# evpr_mini_chopped.net
KiCad netlist of a schematic drawn in EAGLE
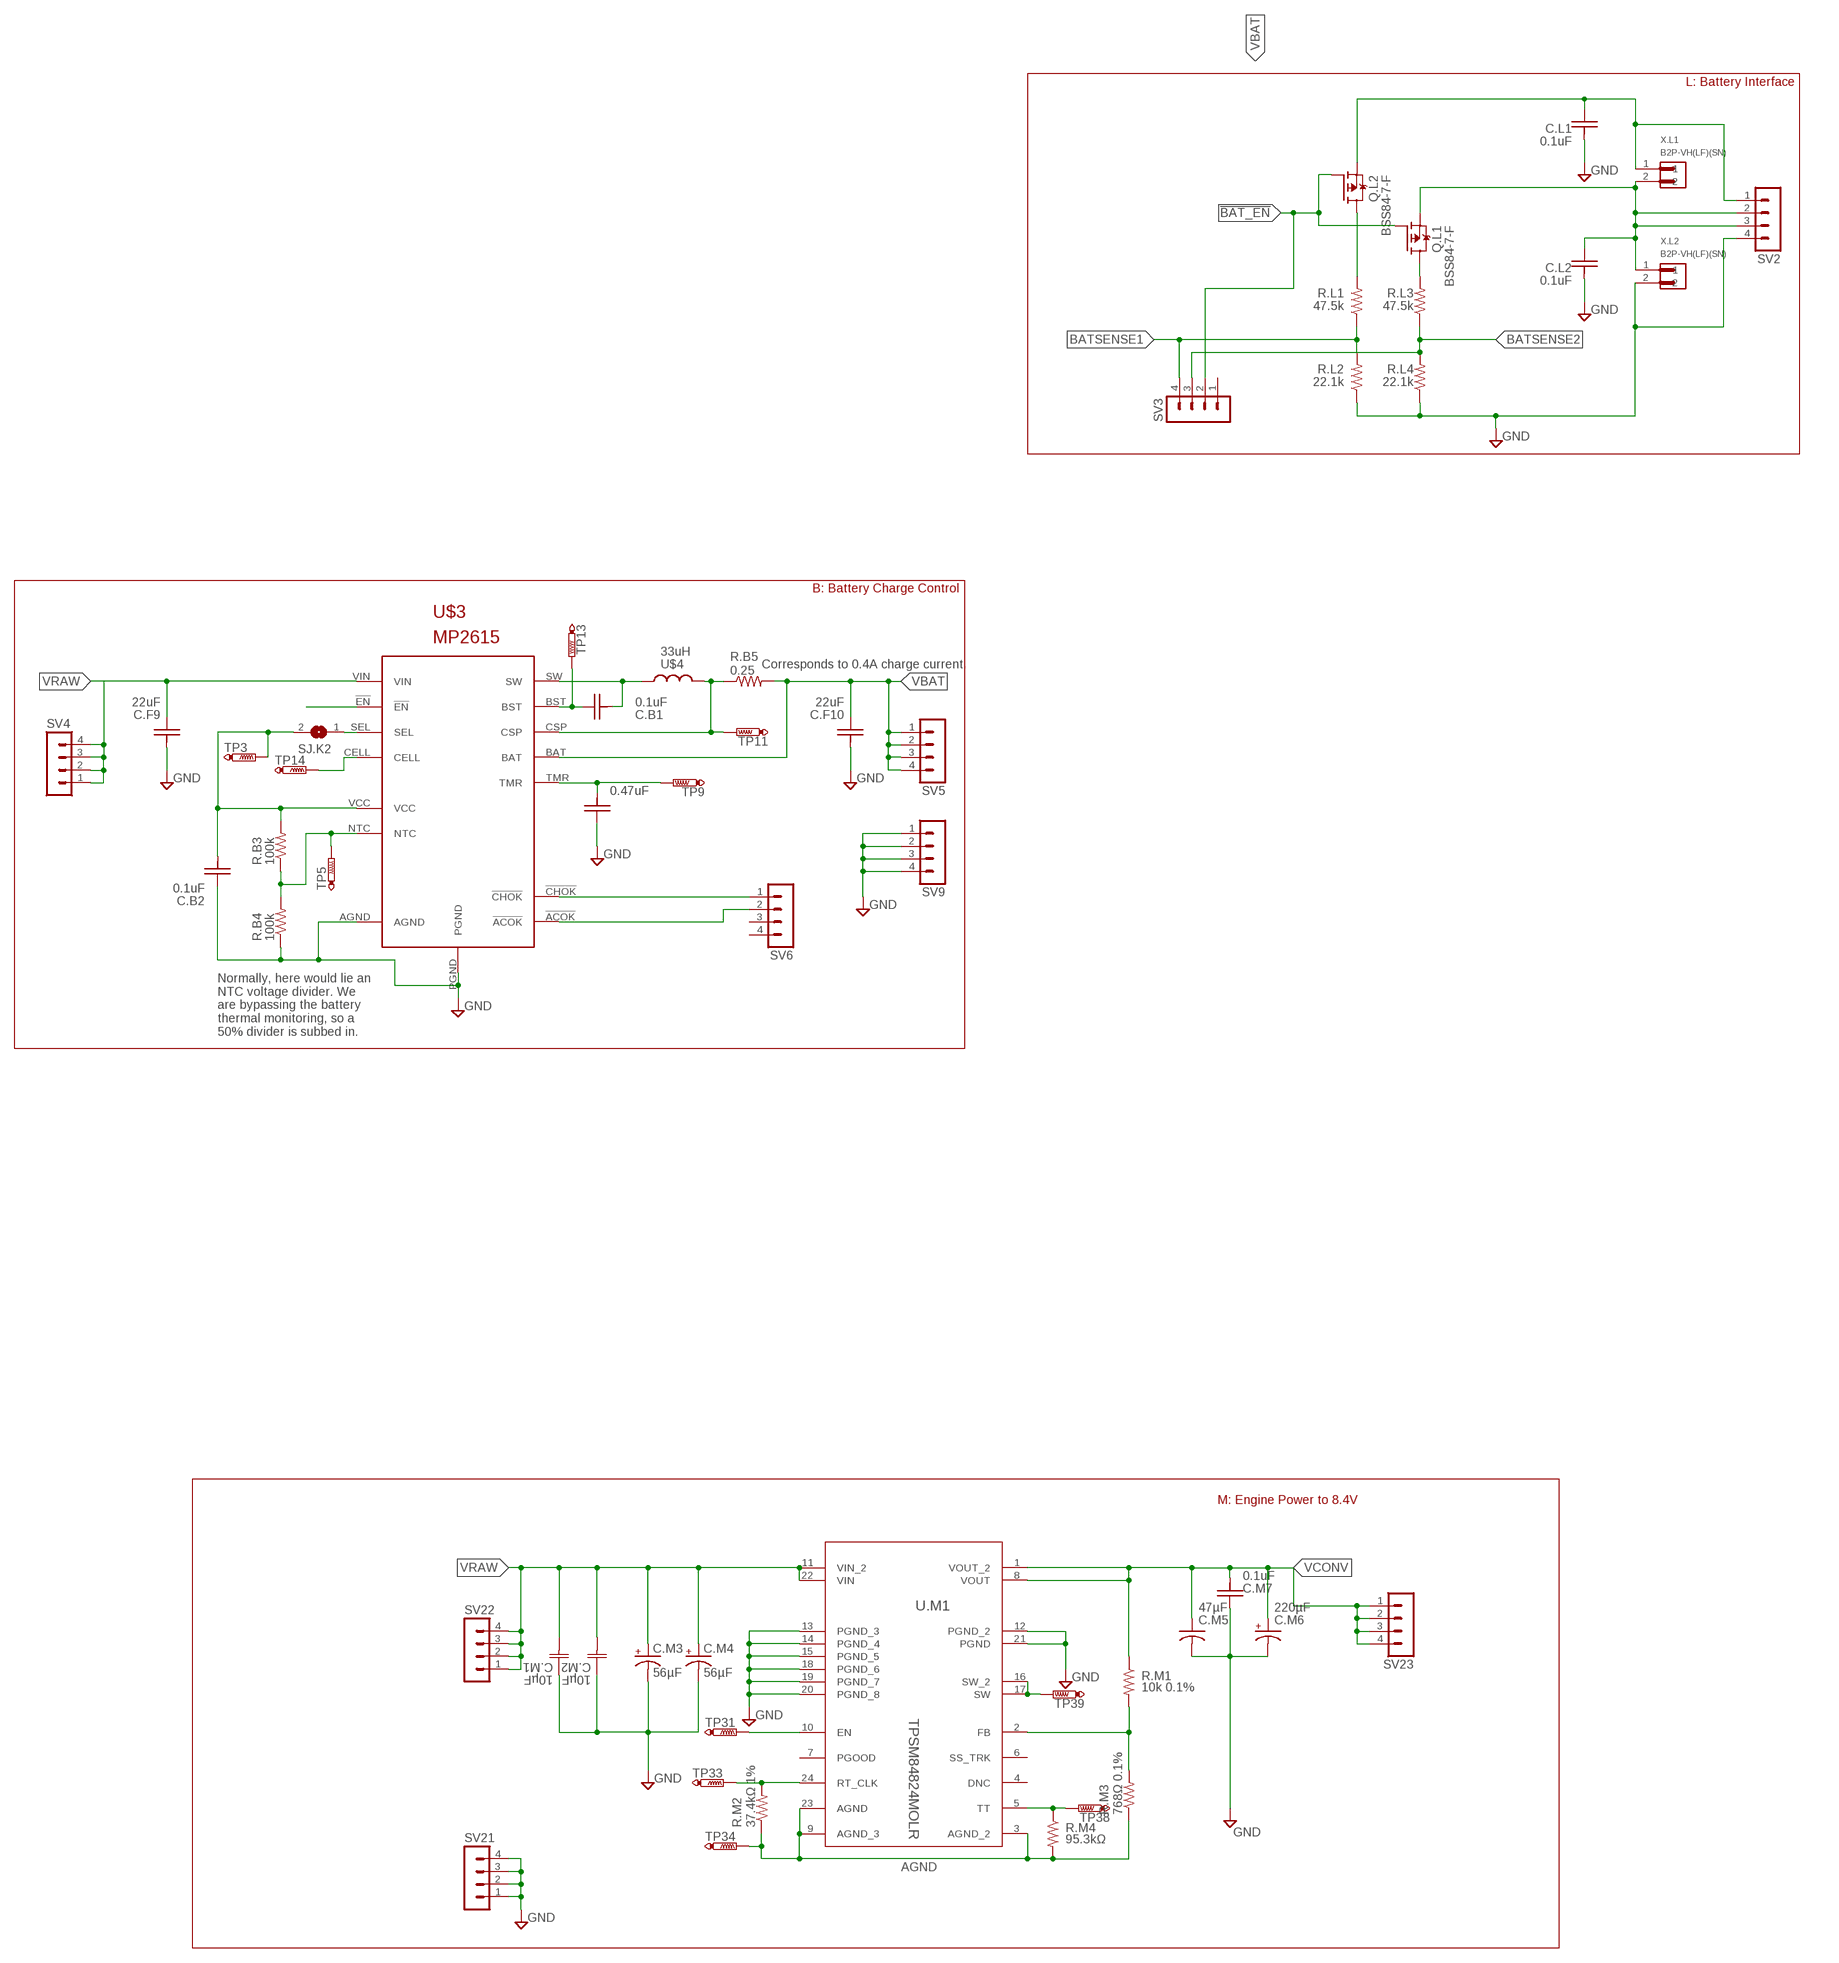
[diagram p0: schematic, sheet 1]

(export (version "E")
  (design (tool "Eeschema 10.0.6"))
  (components
    (comp (ref "C.B1")
      (value "0.1uF")
      (footprint "eagle-import:C0603")
      (libsource (lib "eagle-import") (part "C0603"))
    )
    (comp (ref "C.B2")
      (value "0.1uF")
      (footprint "eagle-import:C0603")
      (libsource (lib "eagle-import") (part "C0603"))
    )
    (comp (ref "C.F9")
      (value "22uF")
      (footprint "eagle-import:C0603")
      (libsource (lib "eagle-import") (part "C0603"))
    )
    (comp (ref "C.F10")
      (value "22uF")
      (footprint "eagle-import:C0603")
      (libsource (lib "eagle-import") (part "C0603"))
    )
    (comp (ref "C.J3")
      (value "0.47uF")
      (footprint "eagle-import:C0603")
      (libsource (lib "eagle-import") (part "C0603"))
    )
    (comp (ref "C.L1")
      (value "0.1uF")
      (footprint "eagle-import:C0603")
      (libsource (lib "eagle-import") (part "C0603"))
    )
    (comp (ref "C.L2")
      (value "0.1uF")
      (footprint "eagle-import:C0603")
      (libsource (lib "eagle-import") (part "C0603"))
    )
    (comp (ref "C.M1")
      (value "10µF")
      (footprint "eagle-import:CAP_3225")
      (libsource (lib "eagle-import") (part "C3225X7R1E106K250AC"))
    )
    (comp (ref "C.M2")
      (value "10µF")
      (footprint "eagle-import:CAP_3225")
      (libsource (lib "eagle-import") (part "C3225X7R1E106K250AC"))
    )
    (comp (ref "C.M3")
      (value "56µF")
      (footprint "eagle-import:OSCON_SVPF_6.3MM")
      (libsource (lib "eagle-import") (part "6.3MMCAP"))
    )
    (comp (ref "C.M4")
      (value "56µF")
      (footprint "eagle-import:OSCON_SVPF_6.3MM")
      (libsource (lib "eagle-import") (part "6.3MMCAP"))
    )
    (comp (ref "C.M5")
      (value "47µF")
      (footprint "eagle-import:C1210")
      (libsource (lib "eagle-import") (part "C-USC1210"))
    )
    (comp (ref "C.M6")
      (value "220µF")
      (footprint "eagle-import:C6CYLCAP")
      (libsource (lib "eagle-import") (part "WURTH875115352003"))
    )
    (comp (ref "C.M7")
      (value "0.1uF")
      (footprint "eagle-import:C0603")
      (libsource (lib "eagle-import") (part "C0603"))
    )
    (comp (ref "Q.L1")
      (value "BSS84-7-F")
      (footprint "eagle-import:SOT23")
      (libsource (lib "eagle-import") (part "BSS84-7-F"))
    )
    (comp (ref "Q.L2")
      (value "BSS84-7-F")
      (footprint "eagle-import:SOT23")
      (libsource (lib "eagle-import") (part "BSS84-7-F"))
    )
    (comp (ref "R.B3")
      (value "100k")
      (footprint "eagle-import:R0603")
      (libsource (lib "eagle-import") (part "R0603"))
    )
    (comp (ref "R.B4")
      (value "100k")
      (footprint "eagle-import:R0603")
      (libsource (lib "eagle-import") (part "R0603"))
    )
    (comp (ref "R.B5")
      (value "0.25")
      (footprint "eagle-import:R0603")
      (libsource (lib "eagle-import") (part "R0603"))
    )
    (comp (ref "R.L1")
      (value "47.5k")
      (footprint "eagle-import:R0603")
      (libsource (lib "eagle-import") (part "R0603"))
    )
    (comp (ref "R.L2")
      (value "22.1k")
      (footprint "eagle-import:R0603")
      (libsource (lib "eagle-import") (part "R0603"))
    )
    (comp (ref "R.L3")
      (value "47.5k")
      (footprint "eagle-import:R0603")
      (libsource (lib "eagle-import") (part "R0603"))
    )
    (comp (ref "R.L4")
      (value "22.1k")
      (footprint "eagle-import:R0603")
      (libsource (lib "eagle-import") (part "R0603"))
    )
    (comp (ref "R.M1")
      (value "10k 0.1%")
      (footprint "eagle-import:R0603")
      (libsource (lib "eagle-import") (part "R0603"))
    )
    (comp (ref "R.M2")
      (value "37.4kΩ 1%")
      (footprint "eagle-import:R0603")
      (libsource (lib "eagle-import") (part "R0603"))
    )
    (comp (ref "R.M3")
      (value "768Ω 0.1%")
      (footprint "eagle-import:R0603")
      (libsource (lib "eagle-import") (part "R0603"))
    )
    (comp (ref "R.M4")
      (value "95.3kΩ")
      (footprint "eagle-import:R0603")
      (libsource (lib "eagle-import") (part "R0603"))
    )
    (comp (ref "SJ.K2")
      (value "SJ")
      (footprint "eagle-import:SJ")
      (libsource (lib "eagle-import") (part "SJ"))
    )
    (comp (ref "SV2")
      (value "MA04-1")
      (footprint "eagle-import:MA04-1")
      (libsource (lib "eagle-import") (part "MA04-1"))
    )
    (comp (ref "SV3")
      (value "MA04-1")
      (footprint "eagle-import:MA04-1")
      (libsource (lib "eagle-import") (part "MA04-1"))
    )
    (comp (ref "SV4")
      (value "MA04-1")
      (footprint "eagle-import:MA04-1")
      (libsource (lib "eagle-import") (part "MA04-1"))
    )
    (comp (ref "SV5")
      (value "MA04-1")
      (footprint "eagle-import:MA04-1")
      (libsource (lib "eagle-import") (part "MA04-1"))
    )
    (comp (ref "SV6")
      (value "MA04-1")
      (footprint "eagle-import:MA04-1")
      (libsource (lib "eagle-import") (part "MA04-1"))
    )
    (comp (ref "SV9")
      (value "MA04-1")
      (footprint "eagle-import:MA04-1")
      (libsource (lib "eagle-import") (part "MA04-1"))
    )
    (comp (ref "SV21")
      (value "MA04-1")
      (footprint "eagle-import:MA04-1")
      (libsource (lib "eagle-import") (part "MA04-1"))
    )
    (comp (ref "SV22")
      (value "MA04-1")
      (footprint "eagle-import:MA04-1")
      (libsource (lib "eagle-import") (part "MA04-1"))
    )
    (comp (ref "SV23")
      (value "MA04-1")
      (footprint "eagle-import:MA04-1")
      (libsource (lib "eagle-import") (part "MA04-1"))
    )
    (comp (ref "TP3")
      (value "PTR1TP10R")
      (footprint "eagle-import:TP10R")
      (libsource (lib "eagle-import") (part "PTR1TP10R"))
    )
    (comp (ref "TP5")
      (value "PTR1TP10R")
      (footprint "eagle-import:TP10R")
      (libsource (lib "eagle-import") (part "PTR1TP10R"))
    )
    (comp (ref "TP9")
      (value "PTR1TP10R")
      (footprint "eagle-import:TP10R")
      (libsource (lib "eagle-import") (part "PTR1TP10R"))
    )
    (comp (ref "TP11")
      (value "PTR1TP10R")
      (footprint "eagle-import:TP10R")
      (libsource (lib "eagle-import") (part "PTR1TP10R"))
    )
    (comp (ref "TP13")
      (value "PTR1TP10R")
      (footprint "eagle-import:TP10R")
      (libsource (lib "eagle-import") (part "PTR1TP10R"))
    )
    (comp (ref "TP14")
      (value "PTR1TP10R")
      (footprint "eagle-import:TP10R")
      (libsource (lib "eagle-import") (part "PTR1TP10R"))
    )
    (comp (ref "TP31")
      (value "PTR1TP10R")
      (footprint "eagle-import:TP10R")
      (libsource (lib "eagle-import") (part "PTR1TP10R"))
    )
    (comp (ref "TP33")
      (value "PTR1TP10R")
      (footprint "eagle-import:TP10R")
      (libsource (lib "eagle-import") (part "PTR1TP10R"))
    )
    (comp (ref "TP34")
      (value "PTR1TP10R")
      (footprint "eagle-import:TP10R")
      (libsource (lib "eagle-import") (part "PTR1TP10R"))
    )
    (comp (ref "TP38")
      (value "PTR1TP10R")
      (footprint "eagle-import:TP10R")
      (libsource (lib "eagle-import") (part "PTR1TP10R"))
    )
    (comp (ref "TP39")
      (value "PTR1TP10R")
      (footprint "eagle-import:TP10R")
      (libsource (lib "eagle-import") (part "PTR1TP10R"))
    )
    (comp (ref "U$3")
      (value "MP2615")
      (footprint "eagle-import:QFN16")
      (libsource (lib "eagle-import") (part "MP2615"))
    )
    (comp (ref "U$4")
      (value "33uH")
      (footprint "eagle-import:SRN5040TA")
      (libsource (lib "eagle-import") (part "SRN5040TA-330M"))
    )
    (comp (ref "U.M1")
      (value "TPSM84824MOLR")
      (footprint "eagle-import:MOL0024A")
      (libsource (lib "eagle-import") (part "TPSM84824MOLR"))
    )
    (comp (ref "X.L1")
      (value "B2P-VH(LF)(SN)")
      (footprint "eagle-import:JST_B2P-VH(LF)(SN)")
      (fields (field (name "MF") "JST Sales") (field (name "MP") "B2P-VH_LF__SN_"))
      (libsource (lib "eagle-import") (part "B2P-VH(LF)(SN)"))
    )
    (comp (ref "X.L2")
      (value "B2P-VH(LF)(SN)")
      (footprint "eagle-import:JST_B2P-VH(LF)(SN)")
      (fields (field (name "MF") "JST Sales") (field (name "MP") "B2P-VH_LF__SN_"))
      (libsource (lib "eagle-import") (part "B2P-VH(LF)(SN)"))
    )
  )
  (nets
    (net (code "1") (name "/AGND") (class "Default")
      (node (ref "R.M2") (pin "1") (pinfunction "1_1") (pintype "passive"))
      (node (ref "R.M3") (pin "1") (pinfunction "1_1") (pintype "passive"))
      (node (ref "R.M4") (pin "2") (pinfunction "2_2") (pintype "passive"))
      (node (ref "TP34") (pin "TP") (pinfunction "TP_TP") (pintype "input"))
      (node (ref "U.M1") (pin "23") (pinfunction "AGND_23") (pintype "power_in"))
      (node (ref "U.M1") (pin "3") (pinfunction "AGND_2_3") (pintype "power_in"))
      (node (ref "U.M1") (pin "9") (pinfunction "AGND_3_9") (pintype "power_in"))
    )
    (net (code "2") (name "/~{BAT_EN}") (class "Default")
      (node (ref "Q.L1") (pin "1") (pinfunction "G_1") (pintype "passive"))
      (node (ref "Q.L2") (pin "1") (pinfunction "G_1") (pintype "passive"))
      (node (ref "SV3") (pin "2") (pinfunction "2_2") (pintype "passive"))
    )
    (net (code "3") (name "BATSENSE1") (class "Default")
      (node (ref "R.L1") (pin "1") (pinfunction "1_1") (pintype "passive"))
      (node (ref "R.L2") (pin "2") (pinfunction "2_2") (pintype "passive"))
      (node (ref "SV3") (pin "4") (pinfunction "4_4") (pintype "passive"))
    )
    (net (code "4") (name "BATSENSE2") (class "Default")
      (node (ref "R.L3") (pin "1") (pinfunction "1_1") (pintype "passive"))
      (node (ref "R.L4") (pin "2") (pinfunction "2_2") (pintype "passive"))
      (node (ref "SV3") (pin "3") (pinfunction "3_3") (pintype "passive"))
    )
    (net (code "5") (name "GND") (class "Default")
      (node (ref "C.B2") (pin "1") (pinfunction "1_1") (pintype "passive"))
      (node (ref "C.F10") (pin "2") (pinfunction "2_2") (pintype "passive"))
      (node (ref "C.F9") (pin "2") (pinfunction "2_2") (pintype "passive"))
      (node (ref "C.J3") (pin "1") (pinfunction "1_1") (pintype "passive"))
      (node (ref "C.L1") (pin "2") (pinfunction "2_2") (pintype "passive"))
      (node (ref "C.L2") (pin "2") (pinfunction "2_2") (pintype "passive"))
      (node (ref "C.M1") (pin "1") (pinfunction "1_1") (pintype "passive"))
      (node (ref "C.M2") (pin "1") (pinfunction "1_1") (pintype "passive"))
      (node (ref "C.M3") (pin "-") (pinfunction "-_-") (pintype "passive"))
      (node (ref "C.M4") (pin "-") (pinfunction "-_-") (pintype "passive"))
      (node (ref "C.M5") (pin "2") (pinfunction "2_2") (pintype "passive"))
      (node (ref "C.M6") (pin "P$1") (pinfunction "-_P$1") (pintype "passive"))
      (node (ref "C.M7") (pin "1") (pinfunction "1_1") (pintype "passive"))
      (node (ref "R.B4") (pin "1") (pinfunction "1_1") (pintype "passive"))
      (node (ref "R.L2") (pin "1") (pinfunction "1_1") (pintype "passive"))
      (node (ref "R.L4") (pin "1") (pinfunction "1_1") (pintype "passive"))
      (node (ref "SV2") (pin "4") (pinfunction "4_4") (pintype "passive"))
      (node (ref "SV21") (pin "1") (pinfunction "1_1") (pintype "passive"))
      (node (ref "SV21") (pin "2") (pinfunction "2_2") (pintype "passive"))
      (node (ref "SV21") (pin "3") (pinfunction "3_3") (pintype "passive"))
      (node (ref "SV21") (pin "4") (pinfunction "4_4") (pintype "passive"))
      (node (ref "SV9") (pin "1") (pinfunction "1_1") (pintype "passive"))
      (node (ref "SV9") (pin "2") (pinfunction "2_2") (pintype "passive"))
      (node (ref "SV9") (pin "3") (pinfunction "3_3") (pintype "passive"))
      (node (ref "SV9") (pin "4") (pinfunction "4_4") (pintype "passive"))
      (node (ref "U$3") (pin "AGND") (pinfunction "AGND_AGND") (pintype "bidirectional"))
      (node (ref "U$3") (pin "PGND") (pinfunction "PGND_PGND") (pintype "bidirectional"))
      (node (ref "U.M1") (pin "12") (pinfunction "PGND_2_12") (pintype "power_in"))
      (node (ref "U.M1") (pin "13") (pinfunction "PGND_3_13") (pintype "power_in"))
      (node (ref "U.M1") (pin "14") (pinfunction "PGND_4_14") (pintype "power_in"))
      (node (ref "U.M1") (pin "15") (pinfunction "PGND_5_15") (pintype "power_in"))
      (node (ref "U.M1") (pin "18") (pinfunction "PGND_6_18") (pintype "power_in"))
      (node (ref "U.M1") (pin "19") (pinfunction "PGND_7_19") (pintype "power_in"))
      (node (ref "U.M1") (pin "20") (pinfunction "PGND_8_20") (pintype "power_in"))
      (node (ref "U.M1") (pin "21") (pinfunction "PGND_21") (pintype "power_in"))
      (node (ref "X.L2") (pin "2") (pinfunction "2_2") (pintype "passive"))
    )
    (net (code "6") (name "Net-(C.B1-Pad1)") (class "Default")
      (node (ref "C.B1") (pin "1") (pinfunction "1_1") (pintype "passive"))
      (node (ref "TP13") (pin "TP") (pinfunction "TP_TP") (pintype "input"))
      (node (ref "U$3") (pin "BST") (pinfunction "BST_BST") (pintype "bidirectional"))
    )
    (net (code "7") (name "Net-(C.B2-Pad2)") (class "Default")
      (node (ref "C.B2") (pin "2") (pinfunction "2_2") (pintype "passive"))
      (node (ref "R.B3") (pin "2") (pinfunction "2_2") (pintype "passive"))
      (node (ref "SJ.K2") (pin "2") (pinfunction "2_2") (pintype "passive"))
      (node (ref "TP3") (pin "TP") (pinfunction "TP_TP") (pintype "input"))
      (node (ref "U$3") (pin "VCC") (pinfunction "VCC_VCC") (pintype "bidirectional"))
    )
    (net (code "8") (name "Net-(C.J3-Pad2)") (class "Default")
      (node (ref "C.J3") (pin "2") (pinfunction "2_2") (pintype "passive"))
      (node (ref "TP9") (pin "TP") (pinfunction "TP_TP") (pintype "input"))
      (node (ref "U$3") (pin "TMR") (pinfunction "TMR_TMR") (pintype "bidirectional"))
    )
    (net (code "9") (name "Net-(Q.L1-D)") (class "Default")
      (node (ref "Q.L1") (pin "3") (pinfunction "D_3") (pintype "passive"))
      (node (ref "R.L3") (pin "2") (pinfunction "2_2") (pintype "passive"))
    )
    (net (code "10") (name "Net-(Q.L1-S)") (class "Default")
      (node (ref "C.L2") (pin "1") (pinfunction "1_1") (pintype "passive"))
      (node (ref "Q.L1") (pin "2") (pinfunction "S_2") (pintype "passive"))
      (node (ref "SV2") (pin "2") (pinfunction "2_2") (pintype "passive"))
      (node (ref "SV2") (pin "3") (pinfunction "3_3") (pintype "passive"))
      (node (ref "X.L1") (pin "2") (pinfunction "2_2") (pintype "passive"))
      (node (ref "X.L2") (pin "1") (pinfunction "1_1") (pintype "passive"))
    )
    (net (code "11") (name "Net-(Q.L2-D)") (class "Default")
      (node (ref "Q.L2") (pin "3") (pinfunction "D_3") (pintype "passive"))
      (node (ref "R.L1") (pin "2") (pinfunction "2_2") (pintype "passive"))
    )
    (net (code "12") (name "Net-(R.B3-Pad1)") (class "Default")
      (node (ref "R.B3") (pin "1") (pinfunction "1_1") (pintype "passive"))
      (node (ref "R.B4") (pin "2") (pinfunction "2_2") (pintype "passive"))
      (node (ref "TP5") (pin "TP") (pinfunction "TP_TP") (pintype "input"))
      (node (ref "U$3") (pin "NTC") (pinfunction "NTC_NTC") (pintype "bidirectional"))
    )
    (net (code "13") (name "Net-(SJ.K2-Pad1)") (class "Default")
      (node (ref "SJ.K2") (pin "1") (pinfunction "1_1") (pintype "passive"))
      (node (ref "U$3") (pin "SEL") (pinfunction "SEL_SEL") (pintype "bidirectional"))
    )
    (net (code "14") (name "Net-(TP14-PadTP)") (class "Default")
      (node (ref "TP14") (pin "TP") (pinfunction "TP_TP") (pintype "input"))
      (node (ref "U$3") (pin "CELL") (pinfunction "CELL_CELL") (pintype "bidirectional"))
    )
    (net (code "15") (name "Net-(U$3-~{ACOK})") (class "Default")
      (node (ref "SV6") (pin "2") (pinfunction "2_2") (pintype "passive"))
      (node (ref "U$3") (pin "!ACOK") (pinfunction "~{ACOK}_!ACOK") (pintype "bidirectional"))
    )
    (net (code "16") (name "Net-(U$3-~{CHOK})") (class "Default")
      (node (ref "SV6") (pin "1") (pinfunction "1_1") (pintype "passive"))
      (node (ref "U$3") (pin "!CHOK") (pinfunction "~{CHOK}_!CHOK") (pintype "bidirectional"))
    )
    (net (code "17") (name "Net-(U$4-1)") (class "Default")
      (node (ref "C.B1") (pin "2") (pinfunction "2_2") (pintype "passive"))
      (node (ref "U$3") (pin "SW") (pinfunction "SW_SW") (pintype "bidirectional"))
      (node (ref "U$4") (pin "P$1") (pinfunction "1_P$1") (pintype "passive"))
    )
    (net (code "18") (name "Net-(U$4-2)") (class "Default")
      (node (ref "R.B5") (pin "1") (pinfunction "1_1") (pintype "passive"))
      (node (ref "TP11") (pin "TP") (pinfunction "TP_TP") (pintype "input"))
      (node (ref "U$3") (pin "CSP") (pinfunction "CSP_CSP") (pintype "bidirectional"))
      (node (ref "U$4") (pin "P$2") (pinfunction "2_P$2") (pintype "passive"))
    )
    (net (code "19") (name "Net-(U.M1-EN)") (class "Default")
      (node (ref "TP31") (pin "TP") (pinfunction "TP_TP") (pintype "input"))
      (node (ref "U.M1") (pin "10") (pinfunction "EN_10") (pintype "input"))
    )
    (net (code "20") (name "Net-(U.M1-FB)") (class "Default")
      (node (ref "R.M1") (pin "2") (pinfunction "2_2") (pintype "passive"))
      (node (ref "R.M3") (pin "2") (pinfunction "2_2") (pintype "passive"))
      (node (ref "U.M1") (pin "2") (pinfunction "FB_2") (pintype "input"))
    )
    (net (code "21") (name "Net-(U.M1-RT_CLK)") (class "Default")
      (node (ref "R.M2") (pin "2") (pinfunction "2_2") (pintype "passive"))
      (node (ref "TP33") (pin "TP") (pinfunction "TP_TP") (pintype "input"))
      (node (ref "U.M1") (pin "24") (pinfunction "RT_CLK_24") (pintype "input"))
    )
    (net (code "22") (name "Net-(U.M1-SW)") (class "Default")
      (node (ref "TP39") (pin "TP") (pinfunction "TP_TP") (pintype "input"))
      (node (ref "U.M1") (pin "16") (pinfunction "SW_2_16") (pintype "output"))
      (node (ref "U.M1") (pin "17") (pinfunction "SW_17") (pintype "output"))
    )
    (net (code "23") (name "Net-(U.M1-TT)") (class "Default")
      (node (ref "R.M4") (pin "1") (pinfunction "1_1") (pintype "passive"))
      (node (ref "TP38") (pin "TP") (pinfunction "TP_TP") (pintype "input"))
      (node (ref "U.M1") (pin "5") (pinfunction "TT_5") (pintype "passive"))
    )
    (net (code "24") (name "VBAT") (class "Default")
      (node (ref "C.F10") (pin "1") (pinfunction "1_1") (pintype "passive"))
      (node (ref "C.L1") (pin "1") (pinfunction "1_1") (pintype "passive"))
      (node (ref "Q.L2") (pin "2") (pinfunction "S_2") (pintype "passive"))
      (node (ref "R.B5") (pin "2") (pinfunction "2_2") (pintype "passive"))
      (node (ref "SV2") (pin "1") (pinfunction "1_1") (pintype "passive"))
      (node (ref "SV5") (pin "1") (pinfunction "1_1") (pintype "passive"))
      (node (ref "SV5") (pin "2") (pinfunction "2_2") (pintype "passive"))
      (node (ref "SV5") (pin "3") (pinfunction "3_3") (pintype "passive"))
      (node (ref "SV5") (pin "4") (pinfunction "4_4") (pintype "passive"))
      (node (ref "U$3") (pin "BAT") (pinfunction "BAT_BAT") (pintype "bidirectional"))
      (node (ref "X.L1") (pin "1") (pinfunction "1_1") (pintype "passive"))
    )
    (net (code "25") (name "VCONV") (class "Default")
      (node (ref "C.M5") (pin "1") (pinfunction "1_1") (pintype "passive"))
      (node (ref "C.M6") (pin "P$2") (pinfunction "+_P$2") (pintype "passive"))
      (node (ref "C.M7") (pin "2") (pinfunction "2_2") (pintype "passive"))
      (node (ref "R.M1") (pin "1") (pinfunction "1_1") (pintype "passive"))
      (node (ref "SV23") (pin "1") (pinfunction "1_1") (pintype "passive"))
      (node (ref "SV23") (pin "2") (pinfunction "2_2") (pintype "passive"))
      (node (ref "SV23") (pin "3") (pinfunction "3_3") (pintype "passive"))
      (node (ref "SV23") (pin "4") (pinfunction "4_4") (pintype "passive"))
      (node (ref "U.M1") (pin "1") (pinfunction "VOUT_2_1") (pintype "power_in"))
      (node (ref "U.M1") (pin "8") (pinfunction "VOUT_8") (pintype "power_in"))
    )
    (net (code "26") (name "VRAW") (class "Default")
      (node (ref "C.F9") (pin "1") (pinfunction "1_1") (pintype "passive"))
      (node (ref "C.M1") (pin "2") (pinfunction "2_2") (pintype "passive"))
      (node (ref "C.M2") (pin "2") (pinfunction "2_2") (pintype "passive"))
      (node (ref "C.M3") (pin "+") (pinfunction "+_+") (pintype "passive"))
      (node (ref "C.M4") (pin "+") (pinfunction "+_+") (pintype "passive"))
      (node (ref "SV22") (pin "1") (pinfunction "1_1") (pintype "passive"))
      (node (ref "SV22") (pin "2") (pinfunction "2_2") (pintype "passive"))
      (node (ref "SV22") (pin "3") (pinfunction "3_3") (pintype "passive"))
      (node (ref "SV22") (pin "4") (pinfunction "4_4") (pintype "passive"))
      (node (ref "SV4") (pin "1") (pinfunction "1_1") (pintype "passive"))
      (node (ref "SV4") (pin "2") (pinfunction "2_2") (pintype "passive"))
      (node (ref "SV4") (pin "3") (pinfunction "3_3") (pintype "passive"))
      (node (ref "SV4") (pin "4") (pinfunction "4_4") (pintype "passive"))
      (node (ref "U$3") (pin "VIN") (pinfunction "VIN_VIN") (pintype "bidirectional"))
      (node (ref "U.M1") (pin "11") (pinfunction "VIN_2_11") (pintype "power_in"))
      (node (ref "U.M1") (pin "22") (pinfunction "VIN_22") (pintype "power_in"))
    )
    (net (code "27") (name "unconnected-(SV3-Pad1)") (class "Default")
      (node (ref "SV3") (pin "1") (pinfunction "1_1") (pintype "passive"))
    )
    (net (code "28") (name "unconnected-(SV6-Pad3)") (class "Default")
      (node (ref "SV6") (pin "3") (pinfunction "3_3") (pintype "passive"))
    )
    (net (code "29") (name "unconnected-(SV6-Pad4)") (class "Default")
      (node (ref "SV6") (pin "4") (pinfunction "4_4") (pintype "passive"))
    )
    (net (code "30") (name "unconnected-(U$3-~{EN}-Pad!EN)") (class "Default")
      (node (ref "U$3") (pin "!EN") (pinfunction "~{EN}_!EN") (pintype "bidirectional"))
    )
    (net (code "31") (name "unconnected-(U.M1-DNC-Pad4)") (class "Default")
      (node (ref "U.M1") (pin "4") (pinfunction "DNC_4") (pintype "passive"))
    )
    (net (code "32") (name "unconnected-(U.M1-PGOOD-Pad7)") (class "Default")
      (node (ref "U.M1") (pin "7") (pinfunction "PGOOD_7") (pintype "passive"))
    )
    (net (code "33") (name "unconnected-(U.M1-SS_TRK-Pad6)") (class "Default")
      (node (ref "U.M1") (pin "6") (pinfunction "SS_TRK_6") (pintype "passive"))
    )
  )
)
